# RGB_LED.net
KiCad netlist of a schematic drawn in Altium Designer
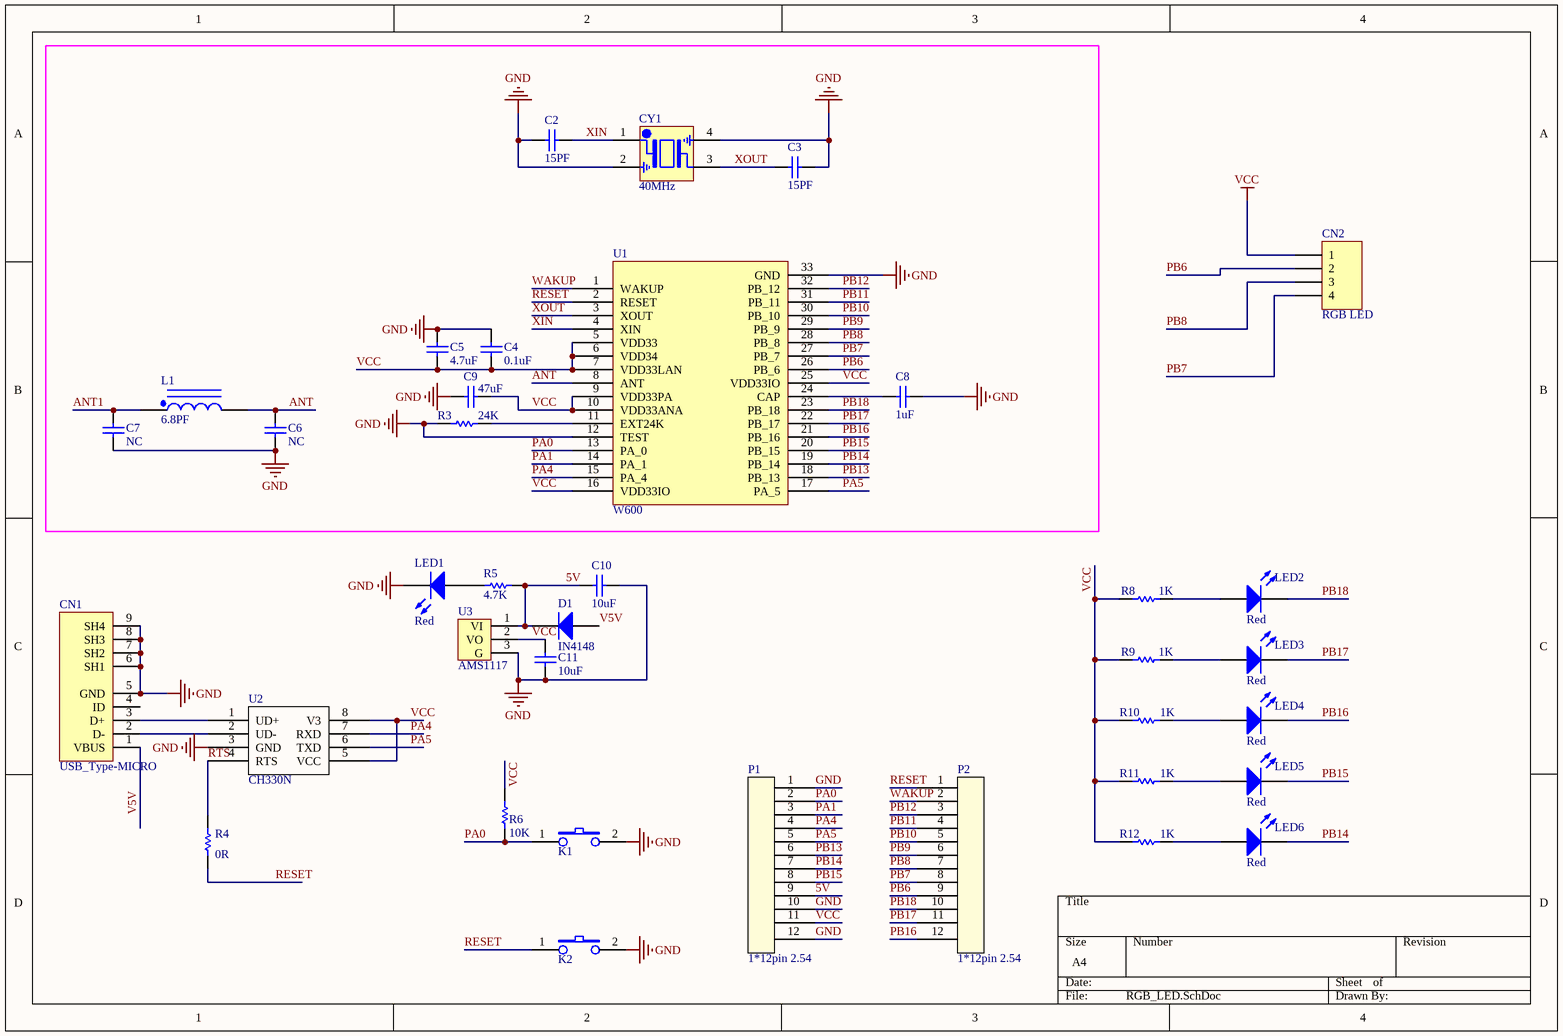
[diagram p0: RGB_LED.SchDoc]

(export (version "E")
  (design (tool "Eeschema 10.0.6"))
  (components
    (comp (ref "C2") (value "15PF") (footprint "0402C") (libsource (lib "My_Lib") (part "CAP")))
    (comp (ref "C3") (value "15PF") (footprint "0402C") (libsource (lib "My_Lib") (part "CAP")))
    (comp (ref "C4") (value "0.1uF") (footprint "0402C") (libsource (lib "My_Lib") (part "CAP")))
    (comp (ref "C5") (value "4.7uF") (footprint "0603C") (libsource (lib "My_Lib") (part "CAP")))
    (comp (ref "C6") (value "NC") (footprint "0402C") (libsource (lib "My_Lib") (part "CAP")))
    (comp (ref "C7") (value "NC") (footprint "0402C") (libsource (lib "My_Lib") (part "CAP")))
    (comp (ref "C8") (value "1uF") (footprint "0402C") (libsource (lib "My_Lib") (part "CAP")))
    (comp (ref "C9") (value "47uF") (footprint "0805C") (libsource (lib "My_Lib") (part "CAP")))
    (comp (ref "C10") (value "10uF") (footprint "0603C") (libsource (lib "My_Lib") (part "CAP")))
    (comp (ref "C11") (value "10uF") (footprint "0603C") (libsource (lib "My_Lib") (part "CAP")))
    (comp (ref "CN1")
      (value "USB_Type-MICRO")
      (footprint "MICRO_USB_DIPB")
      (libsource (lib "My_Lib") (part "USB_Type-MICRO"))
    )
    (comp (ref "CN2")
      (value "RGB LED")
      (footprint "HDR1X4")
      (description "Header, 4-Pin")
      (fields (field (name "PUBLISHER") "Altium Limited"))
      (libsource (lib "Miscellaneous Connectors") (part "Header 4"))
    )
    (comp (ref "CY1") (value "40MHz") (footprint "CY3225") (libsource (lib "My_Lib") (part "CY3225")))
    (comp (ref "D1") (value "IN4148") (footprint "1n5819") (libsource (lib "My_Lib") (part "IN4148")))
    (comp (ref "K1") (value "Button") (footprint "BUTTON3*4*2") (libsource (lib "My_Lib") (part "Button")))
    (comp (ref "K2") (value "Button") (footprint "BUTTON3*4*2") (libsource (lib "My_Lib") (part "Button")))
    (comp (ref "L1") (value "6.8PF") (footprint "0402L") (libsource (lib "My_Lib") (part "L")))
    (comp (ref "LED1") (value "Red") (footprint "0603LED") (libsource (lib "My_Lib") (part "LED")))
    (comp (ref "LED2") (value "Red") (footprint "0603LED") (libsource (lib "My_Lib") (part "LED")))
    (comp (ref "LED3") (value "Red") (footprint "0603LED") (libsource (lib "My_Lib") (part "LED")))
    (comp (ref "LED4") (value "Red") (footprint "0603LED") (libsource (lib "My_Lib") (part "LED")))
    (comp (ref "LED5") (value "Red") (footprint "0603LED") (libsource (lib "My_Lib") (part "LED")))
    (comp (ref "LED6") (value "Red") (footprint "0603LED") (libsource (lib "My_Lib") (part "LED")))
    (comp (ref "P1")
      (value "1*12pin 2.54")
      (footprint "1*12PIN 2.54")
      (libsource (lib "") (part "1*12pin 2.54_1"))
    )
    (comp (ref "P2")
      (value "1*12pin 2.54")
      (footprint "1*12PIN 2.54")
      (libsource (lib "My_Lib") (part "1*12pin 2.54"))
    )
    (comp (ref "R3") (value "24K") (footprint "0402R") (libsource (lib "My_Lib") (part "RES")))
    (comp (ref "R4") (value "0R") (footprint "0402R") (libsource (lib "My_Lib") (part "RES")))
    (comp (ref "R5") (value "4.7K") (footprint "0402R") (libsource (lib "My_Lib") (part "RES")))
    (comp (ref "R6") (value "10K") (footprint "0402R") (libsource (lib "My_Lib") (part "RES")))
    (comp (ref "R8") (value "1K") (footprint "0402R") (libsource (lib "My_Lib") (part "RES")))
    (comp (ref "R9") (value "1K") (footprint "0402R") (libsource (lib "My_Lib") (part "RES")))
    (comp (ref "R10") (value "1K") (footprint "0402R") (libsource (lib "My_Lib") (part "RES")))
    (comp (ref "R11") (value "1K") (footprint "0402R") (libsource (lib "My_Lib") (part "RES")))
    (comp (ref "R12") (value "1K") (footprint "0402R") (libsource (lib "My_Lib") (part "RES")))
    (comp (ref "U1") (value "W600") (footprint "W600") (libsource (lib "My_Lib") (part "W600")))
    (comp (ref "U2") (value "CH330N") (footprint "CH330N") (libsource (lib "My_Lib") (part "CH330N")))
    (comp (ref "U3") (value "AMS1117") (footprint "AMS1117") (libsource (lib "Integrated") (part "AMS1117")))
  )
  (nets
    (net (code "1") (name "/5V") (class "Default")
      (node (ref "C10") (pin "2") (pinfunction "2_2") (pintype "passive"))
      (node (ref "D1") (pin "2") (pinfunction "K_2") (pintype "passive"))
      (node (ref "P1") (pin "9") (pinfunction "9_9") (pintype "passive"))
      (node (ref "R5") (pin "2") (pinfunction "2_2") (pintype "passive"))
      (node (ref "U3") (pin "1") (pinfunction "VI_1") (pintype "passive"))
    )
    (net (code "2") (name "/ANT") (class "Default")
      (node (ref "C6") (pin "2") (pinfunction "2_2") (pintype "passive"))
      (node (ref "L1") (pin "2") (pinfunction "2_2") (pintype "passive"))
      (node (ref "U1") (pin "8") (pinfunction "ANT_8") (pintype "passive"))
    )
    (net (code "3") (name "/ANT1") (class "Default")
      (node (ref "C7") (pin "2") (pinfunction "2_2") (pintype "passive"))
      (node (ref "L1") (pin "1") (pinfunction "1_1") (pintype "passive"))
    )
    (net (code "4") (name "/PA0") (class "Default")
      (node (ref "K1") (pin "1") (pinfunction "A0_1") (pintype "passive"))
      (node (ref "P1") (pin "2") (pinfunction "2_2") (pintype "passive"))
      (node (ref "R6") (pin "1") (pinfunction "1_1") (pintype "passive"))
      (node (ref "U1") (pin "13") (pinfunction "PA_0_13") (pintype "passive"))
    )
    (net (code "5") (name "/PA1") (class "Default")
      (node (ref "P1") (pin "3") (pinfunction "3_3") (pintype "passive"))
      (node (ref "U1") (pin "14") (pinfunction "PA_1_14") (pintype "passive"))
    )
    (net (code "6") (name "/PA4") (class "Default")
      (node (ref "P1") (pin "4") (pinfunction "4_4") (pintype "passive"))
      (node (ref "U1") (pin "15") (pinfunction "PA_4_15") (pintype "passive"))
      (node (ref "U2") (pin "7") (pinfunction "RXD_7") (pintype "passive"))
    )
    (net (code "7") (name "/PA5") (class "Default")
      (node (ref "P1") (pin "5") (pinfunction "5_5") (pintype "passive"))
      (node (ref "U1") (pin "17") (pinfunction "PA_5_17") (pintype "passive"))
      (node (ref "U2") (pin "6") (pinfunction "TXD_6") (pintype "passive"))
    )
    (net (code "8") (name "/PB6") (class "Default")
      (node (ref "CN2") (pin "2") (pinfunction "2_2") (pintype "passive"))
      (node (ref "P2") (pin "9") (pinfunction "9_9") (pintype "passive"))
      (node (ref "U1") (pin "26") (pinfunction "PB_6_26") (pintype "passive"))
    )
    (net (code "9") (name "/PB7") (class "Default")
      (node (ref "CN2") (pin "4") (pinfunction "4_4") (pintype "passive"))
      (node (ref "P2") (pin "8") (pinfunction "8_8") (pintype "passive"))
      (node (ref "U1") (pin "27") (pinfunction "PB_7_27") (pintype "passive"))
    )
    (net (code "10") (name "/PB8") (class "Default")
      (node (ref "CN2") (pin "3") (pinfunction "3_3") (pintype "passive"))
      (node (ref "P2") (pin "7") (pinfunction "7_7") (pintype "passive"))
      (node (ref "U1") (pin "28") (pinfunction "PB_8_28") (pintype "passive"))
    )
    (net (code "11") (name "/PB9") (class "Default")
      (node (ref "P2") (pin "6") (pinfunction "6_6") (pintype "passive"))
      (node (ref "U1") (pin "29") (pinfunction "PB_9_29") (pintype "passive"))
    )
    (net (code "12") (name "/PB10") (class "Default")
      (node (ref "P2") (pin "5") (pinfunction "5_5") (pintype "passive"))
      (node (ref "U1") (pin "30") (pinfunction "PB_10_30") (pintype "passive"))
    )
    (net (code "13") (name "/PB11") (class "Default")
      (node (ref "P2") (pin "4") (pinfunction "4_4") (pintype "passive"))
      (node (ref "U1") (pin "31") (pinfunction "PB_11_31") (pintype "passive"))
    )
    (net (code "14") (name "/PB12") (class "Default")
      (node (ref "P2") (pin "3") (pinfunction "3_3") (pintype "passive"))
      (node (ref "U1") (pin "32") (pinfunction "PB_12_32") (pintype "passive"))
    )
    (net (code "15") (name "/PB13") (class "Default")
      (node (ref "P1") (pin "6") (pinfunction "6_6") (pintype "passive"))
      (node (ref "U1") (pin "18") (pinfunction "PB_13_18") (pintype "passive"))
    )
    (net (code "16") (name "/PB14") (class "Default")
      (node (ref "LED6") (pin "2") (pinfunction "K_2") (pintype "passive"))
      (node (ref "P1") (pin "7") (pinfunction "7_7") (pintype "passive"))
      (node (ref "U1") (pin "19") (pinfunction "PB_14_19") (pintype "passive"))
    )
    (net (code "17") (name "/PB15") (class "Default")
      (node (ref "LED5") (pin "2") (pinfunction "K_2") (pintype "passive"))
      (node (ref "P1") (pin "8") (pinfunction "8_8") (pintype "passive"))
      (node (ref "U1") (pin "20") (pinfunction "PB_15_20") (pintype "passive"))
    )
    (net (code "18") (name "/PB16") (class "Default")
      (node (ref "LED4") (pin "2") (pinfunction "K_2") (pintype "passive"))
      (node (ref "P2") (pin "12") (pinfunction "12_12") (pintype "passive"))
      (node (ref "U1") (pin "21") (pinfunction "PB_16_21") (pintype "passive"))
    )
    (net (code "19") (name "/PB17") (class "Default")
      (node (ref "LED3") (pin "2") (pinfunction "K_2") (pintype "passive"))
      (node (ref "P2") (pin "11") (pinfunction "11_11") (pintype "passive"))
      (node (ref "U1") (pin "22") (pinfunction "PB_17_22") (pintype "passive"))
    )
    (net (code "20") (name "/PB18") (class "Default")
      (node (ref "LED2") (pin "2") (pinfunction "K_2") (pintype "passive"))
      (node (ref "P2") (pin "10") (pinfunction "10_10") (pintype "passive"))
      (node (ref "U1") (pin "23") (pinfunction "PB_18_23") (pintype "passive"))
    )
    (net (code "21") (name "/RESET") (class "Default")
      (node (ref "K2") (pin "1") (pinfunction "A0_1") (pintype "passive"))
      (node (ref "P2") (pin "1") (pintype "passive"))
      (node (ref "R4") (pin "1") (pinfunction "1_1") (pintype "passive"))
      (node (ref "U1") (pin "2") (pinfunction "RESET_2") (pintype "passive"))
    )
    (net (code "22") (name "/RTS") (class "Default")
      (node (ref "R4") (pin "2") (pinfunction "2_2") (pintype "passive"))
      (node (ref "U2") (pin "4") (pinfunction "RTS_4") (pintype "passive"))
    )
    (net (code "23") (name "/V5V") (class "Default")
      (node (ref "CN1") (pin "1") (pinfunction "VBUS_1") (pintype "passive"))
      (node (ref "D1") (pin "1") (pinfunction "A_1") (pintype "passive"))
    )
    (net (code "24") (name "/WAKUP") (class "Default")
      (node (ref "P2") (pin "2") (pinfunction "2_2") (pintype "passive"))
      (node (ref "U1") (pin "1") (pinfunction "WAKUP_1") (pintype "passive"))
    )
    (net (code "25") (name "/XIN") (class "Default")
      (node (ref "C2") (pin "2") (pinfunction "2_2") (pintype "passive"))
      (node (ref "CY1") (pin "1") (pinfunction "IN/OUT_1") (pintype "passive"))
      (node (ref "U1") (pin "4") (pinfunction "XIN_4") (pintype "passive"))
    )
    (net (code "26") (name "/XOUT") (class "Default")
      (node (ref "C3") (pin "1") (pinfunction "1_1") (pintype "passive"))
      (node (ref "CY1") (pin "3") (pinfunction "IN/OUT_3") (pintype "passive"))
      (node (ref "U1") (pin "3") (pinfunction "XOUT_3") (pintype "passive"))
    )
    (net (code "27") (name "GND") (class "Default")
      (node (ref "C10") (pin "1") (pinfunction "1_1") (pintype "passive"))
      (node (ref "C11") (pin "2") (pinfunction "2_2") (pintype "passive"))
      (node (ref "C2") (pin "1") (pinfunction "1_1") (pintype "passive"))
      (node (ref "C3") (pin "2") (pinfunction "2_2") (pintype "passive"))
      (node (ref "C4") (pin "2") (pinfunction "2_2") (pintype "passive"))
      (node (ref "C5") (pin "2") (pinfunction "2_2") (pintype "passive"))
      (node (ref "C6") (pin "1") (pinfunction "1_1") (pintype "passive"))
      (node (ref "C7") (pin "1") (pinfunction "1_1") (pintype "passive"))
      (node (ref "C8") (pin "2") (pinfunction "2_2") (pintype "passive"))
      (node (ref "C9") (pin "1") (pinfunction "1_1") (pintype "passive"))
      (node (ref "CN1") (pin "5") (pinfunction "GND_5") (pintype "passive"))
      (node (ref "CN1") (pin "6") (pinfunction "SH1_6") (pintype "passive"))
      (node (ref "CN1") (pin "7") (pinfunction "SH2_7") (pintype "passive"))
      (node (ref "CN1") (pin "8") (pinfunction "SH3_8") (pintype "passive"))
      (node (ref "CN1") (pin "9") (pinfunction "SH4_9") (pintype "passive"))
      (node (ref "CY1") (pin "2") (pinfunction "GND_2") (pintype "passive"))
      (node (ref "CY1") (pin "4") (pinfunction "GND_4") (pintype "passive"))
      (node (ref "K1") (pin "2") (pinfunction "B0_2") (pintype "passive"))
      (node (ref "K2") (pin "2") (pinfunction "B0_2") (pintype "passive"))
      (node (ref "LED1") (pin "2") (pinfunction "K_2") (pintype "passive"))
      (node (ref "P1") (pin "1") (pintype "passive"))
      (node (ref "P1") (pin "10") (pinfunction "10_10") (pintype "passive"))
      (node (ref "P1") (pin "12") (pinfunction "12_12") (pintype "passive"))
      (node (ref "R3") (pin "1") (pinfunction "1_1") (pintype "passive"))
      (node (ref "U1") (pin "12") (pinfunction "TEST_12") (pintype "passive"))
      (node (ref "U1") (pin "33") (pinfunction "GND_33") (pintype "passive"))
      (node (ref "U2") (pin "3") (pinfunction "GND_3") (pintype "passive"))
      (node (ref "U3") (pin "3") (pinfunction "G_3") (pintype "passive"))
    )
    (net (code "28") (name "Net-(CN1-D+)") (class "Default")
      (node (ref "CN1") (pin "3") (pinfunction "D+_3") (pintype "passive"))
      (node (ref "U2") (pin "1") (pinfunction "UD+_1") (pintype "passive"))
    )
    (net (code "29") (name "Net-(CN1-D-)") (class "Default")
      (node (ref "CN1") (pin "2") (pinfunction "D-_2") (pintype "passive"))
      (node (ref "U2") (pin "2") (pinfunction "UD-_2") (pintype "passive"))
    )
    (net (code "30") (name "Net-(LED1-A)") (class "Default")
      (node (ref "LED1") (pin "1") (pinfunction "A_1") (pintype "passive"))
      (node (ref "R5") (pin "1") (pinfunction "1_1") (pintype "passive"))
    )
    (net (code "31") (name "Net-(LED2-A)") (class "Default")
      (node (ref "LED2") (pin "1") (pinfunction "A_1") (pintype "passive"))
      (node (ref "R8") (pin "1") (pinfunction "1_1") (pintype "passive"))
    )
    (net (code "32") (name "Net-(LED3-A)") (class "Default")
      (node (ref "LED3") (pin "1") (pinfunction "A_1") (pintype "passive"))
      (node (ref "R9") (pin "1") (pinfunction "1_1") (pintype "passive"))
    )
    (net (code "33") (name "Net-(LED4-A)") (class "Default")
      (node (ref "LED4") (pin "1") (pinfunction "A_1") (pintype "passive"))
      (node (ref "R10") (pin "1") (pinfunction "1_1") (pintype "passive"))
    )
    (net (code "34") (name "Net-(LED5-A)") (class "Default")
      (node (ref "LED5") (pin "1") (pinfunction "A_1") (pintype "passive"))
      (node (ref "R11") (pin "1") (pinfunction "1_1") (pintype "passive"))
    )
    (net (code "35") (name "Net-(LED6-A)") (class "Default")
      (node (ref "LED6") (pin "1") (pinfunction "A_1") (pintype "passive"))
      (node (ref "R12") (pin "1") (pinfunction "1_1") (pintype "passive"))
    )
    (net (code "36") (name "Net-(U1-CAP)") (class "Default")
      (node (ref "C8") (pin "1") (pinfunction "1_1") (pintype "passive"))
      (node (ref "U1") (pin "24") (pinfunction "CAP_24") (pintype "passive"))
    )
    (net (code "37") (name "Net-(U1-EXT24K)") (class "Default")
      (node (ref "R3") (pin "2") (pinfunction "2_2") (pintype "passive"))
      (node (ref "U1") (pin "11") (pinfunction "EXT24K_11") (pintype "passive"))
    )
    (net (code "38") (name "VCC") (class "Default")
      (node (ref "C11") (pin "1") (pinfunction "1_1") (pintype "passive"))
      (node (ref "C4") (pin "1") (pinfunction "1_1") (pintype "passive"))
      (node (ref "C5") (pin "1") (pinfunction "1_1") (pintype "passive"))
      (node (ref "C9") (pin "2") (pinfunction "2_2") (pintype "passive"))
      (node (ref "CN2") (pin "1") (pinfunction "1_1") (pintype "passive"))
      (node (ref "P1") (pin "11") (pinfunction "11_11") (pintype "passive"))
      (node (ref "R10") (pin "2") (pinfunction "2_2") (pintype "passive"))
      (node (ref "R11") (pin "2") (pinfunction "2_2") (pintype "passive"))
      (node (ref "R12") (pin "2") (pinfunction "2_2") (pintype "passive"))
      (node (ref "R6") (pin "2") (pinfunction "2_2") (pintype "passive"))
      (node (ref "R8") (pin "2") (pinfunction "2_2") (pintype "passive"))
      (node (ref "R9") (pin "2") (pinfunction "2_2") (pintype "passive"))
      (node (ref "U1") (pin "10") (pinfunction "VDD33ANA_10") (pintype "passive"))
      (node (ref "U1") (pin "16") (pinfunction "VDD33IO_16") (pintype "passive"))
      (node (ref "U1") (pin "25") (pinfunction "VDD33IO_25") (pintype "passive"))
      (node (ref "U1") (pin "5") (pinfunction "VDD33_5") (pintype "passive"))
      (node (ref "U1") (pin "6") (pinfunction "VDD34_6") (pintype "passive"))
      (node (ref "U1") (pin "7") (pinfunction "VDD33LAN_7") (pintype "passive"))
      (node (ref "U1") (pin "9") (pinfunction "VDD33PA_9") (pintype "passive"))
      (node (ref "U2") (pin "5") (pinfunction "VCC_5") (pintype "passive"))
      (node (ref "U2") (pin "8") (pinfunction "V3_8") (pintype "passive"))
      (node (ref "U3") (pin "2") (pinfunction "VO_2") (pintype "passive"))
    )
    (net (code "39") (name "unconnected-(CN1-ID-Pad4)") (class "Default")
      (node (ref "CN1") (pin "4") (pinfunction "ID_4") (pintype "passive"))
    )
  )
)
